# Nano_RC_Receiver.net
KiCad netlist of a schematic drawn in EAGLE
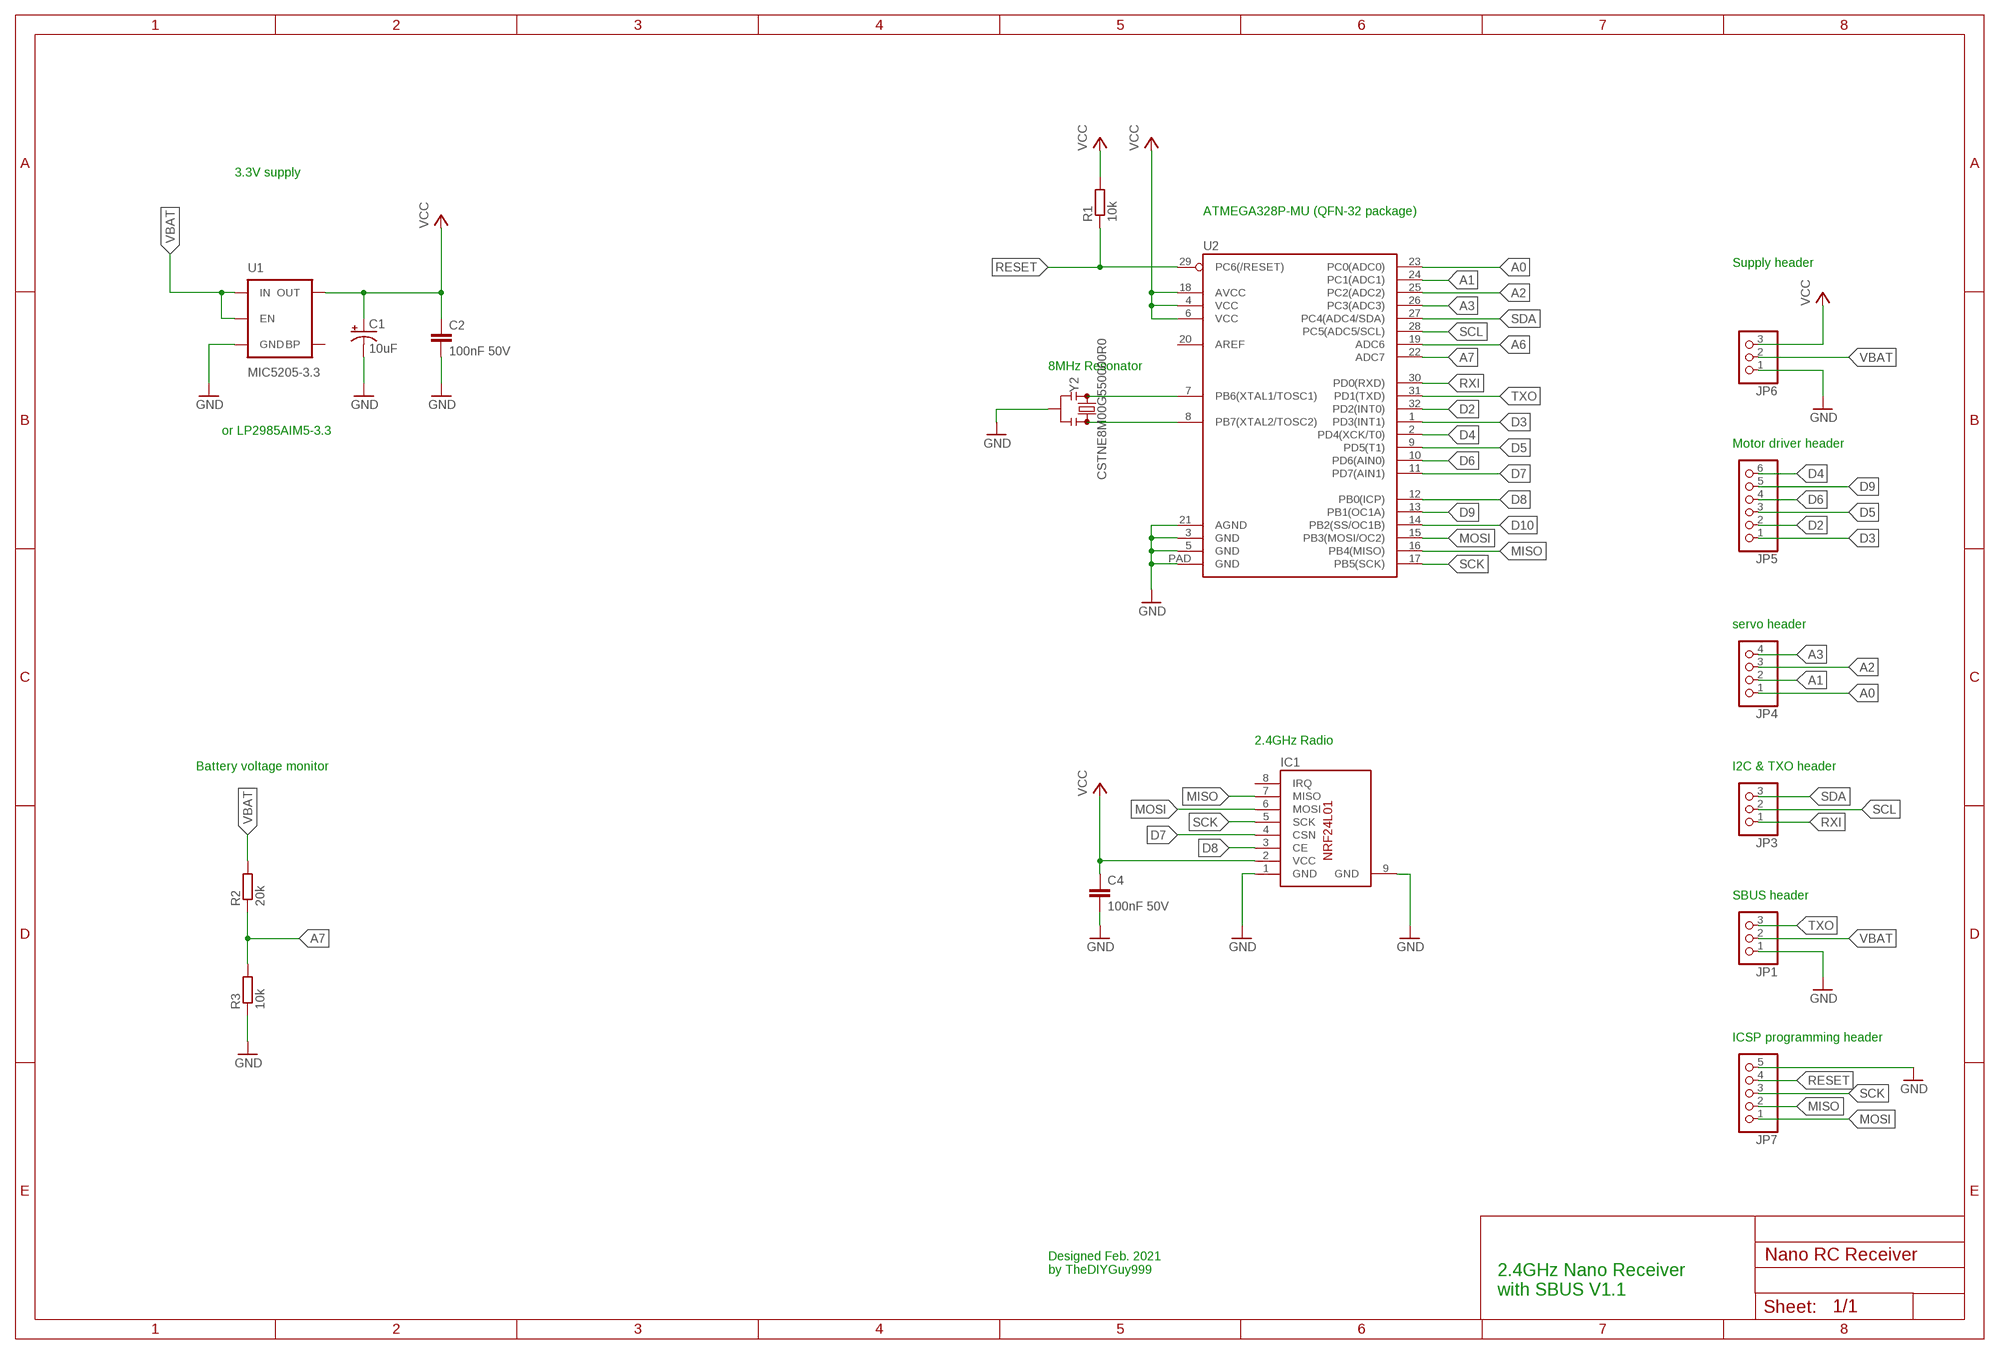
[diagram p0: schematic, sheet 1]

(export (version "E")
  (design (tool "Eeschema 10.0.6"))
  (components
    (comp (ref "C1")
      (value "10uF")
      (footprint "eagle-import:EIA3216")
      (libsource (lib "eagle-import") (part "10UF-16V-10%(TANT)"))
    )
    (comp (ref "C2")
      (value "100nF 50V")
      (footprint "eagle-import:C0603")
      (libsource (lib "eagle-import") (part "C-EUC0603"))
    )
    (comp (ref "C4")
      (value "100nF 50V")
      (footprint "eagle-import:C0603")
      (libsource (lib "eagle-import") (part "C-EUC0603"))
    )
    (comp (ref "IC1")
      (value "NRF24L01SMD_PAD")
      (footprint "eagle-import:NRF24L01_SMD_PAD")
      (libsource (lib "eagle-import") (part "NRF24L01SMD_PAD"))
    )
    (comp (ref "JP1")
      (value "PINHD-1X3SMT")
      (footprint "eagle-import:1X03_SMT")
      (libsource (lib "eagle-import") (part "PINHD-1X3SMT"))
    )
    (comp (ref "JP3")
      (value "PINHD-1X31.27")
      (footprint "eagle-import:1X03_1.27")
      (libsource (lib "eagle-import") (part "PINHD-1X31.27"))
    )
    (comp (ref "JP4")
      (value "PINHD-1X41.27")
      (footprint "eagle-import:1X04_1.27")
      (libsource (lib "eagle-import") (part "PINHD-1X41.27"))
    )
    (comp (ref "JP5")
      (value "PINHD-1X61.27")
      (footprint "eagle-import:1X06_1.27")
      (libsource (lib "eagle-import") (part "PINHD-1X61.27"))
    )
    (comp (ref "JP6")
      (value "PINHD-1X31.27")
      (footprint "eagle-import:1X03_1.27")
      (libsource (lib "eagle-import") (part "PINHD-1X31.27"))
    )
    (comp (ref "JP7")
      (value "PINHD-1X51.27")
      (footprint "eagle-import:1X05_1.27")
      (libsource (lib "eagle-import") (part "PINHD-1X51.27"))
    )
    (comp (ref "R1")
      (value "10k")
      (footprint "eagle-import:R0603")
      (libsource (lib "eagle-import") (part "R-EU_R0603"))
    )
    (comp (ref "R2")
      (value "20k")
      (footprint "eagle-import:R0603")
      (libsource (lib "eagle-import") (part "R-EU_R0603"))
    )
    (comp (ref "R3")
      (value "10k")
      (footprint "eagle-import:R0603")
      (libsource (lib "eagle-import") (part "R-EU_R0603"))
    )
    (comp (ref "U1")
      (value "MIC5205-3.3")
      (footprint "eagle-import:SOT23-5")
      (libsource (lib "eagle-import") (part "MIC52053.3V"))
    )
    (comp (ref "U2")
      (value "ATMEGA328P_MLFMLF32")
      (footprint "eagle-import:MLF32-PAD")
      (libsource (lib "eagle-import") (part "ATMEGA328P_MLFMLF32"))
    )
    (comp (ref "Y2")
      (value "CSTNE8M00G550000R0")
      (footprint "eagle-import:RESONATOR-SMD-3.2X1.3")
      (libsource (lib "eagle-import") (part "RESONATORSMD-3.2X1.3"))
    )
  )
  (nets
    (net (code "1") (name "A0") (class "Default")
      (node (ref "JP4") (pin "1") (pinfunction "1_1") (pintype "passive"))
      (node (ref "U2") (pin "23") (pinfunction "PC0(ADC0)_23") (pintype "bidirectional"))
    )
    (net (code "2") (name "A1") (class "Default")
      (node (ref "JP4") (pin "2") (pinfunction "2_2") (pintype "passive"))
      (node (ref "U2") (pin "24") (pinfunction "PC1(ADC1)_24") (pintype "bidirectional"))
    )
    (net (code "3") (name "A2") (class "Default")
      (node (ref "JP4") (pin "3") (pinfunction "3_3") (pintype "passive"))
      (node (ref "U2") (pin "25") (pinfunction "PC2(ADC2)_25") (pintype "bidirectional"))
    )
    (net (code "4") (name "A3") (class "Default")
      (node (ref "JP4") (pin "4") (pinfunction "4_4") (pintype "passive"))
      (node (ref "U2") (pin "26") (pinfunction "PC3(ADC3)_26") (pintype "bidirectional"))
    )
    (net (code "5") (name "A6") (class "Default")
      (node (ref "U2") (pin "19") (pinfunction "ADC6_19") (pintype "bidirectional"))
    )
    (net (code "6") (name "A7") (class "Default")
      (node (ref "R2") (pin "1") (pinfunction "1_1") (pintype "passive"))
      (node (ref "R3") (pin "2") (pinfunction "2_2") (pintype "passive"))
      (node (ref "U2") (pin "22") (pinfunction "ADC7_22") (pintype "bidirectional"))
    )
    (net (code "7") (name "D2") (class "Default")
      (node (ref "JP5") (pin "2") (pinfunction "2_2") (pintype "passive"))
      (node (ref "U2") (pin "32") (pinfunction "PD2(INT0)_32") (pintype "bidirectional"))
    )
    (net (code "8") (name "D3") (class "Default")
      (node (ref "JP5") (pin "1") (pinfunction "1_1") (pintype "passive"))
      (node (ref "U2") (pin "1") (pinfunction "PD3(INT1)_1") (pintype "bidirectional"))
    )
    (net (code "9") (name "D4") (class "Default")
      (node (ref "JP5") (pin "6") (pinfunction "6_6") (pintype "passive"))
      (node (ref "U2") (pin "2") (pinfunction "PD4(XCK/T0)_2") (pintype "bidirectional"))
    )
    (net (code "10") (name "D5") (class "Default")
      (node (ref "JP5") (pin "3") (pinfunction "3_3") (pintype "passive"))
      (node (ref "U2") (pin "9") (pinfunction "PD5(T1)_9") (pintype "bidirectional"))
    )
    (net (code "11") (name "D6") (class "Default")
      (node (ref "JP5") (pin "4") (pinfunction "4_4") (pintype "passive"))
      (node (ref "U2") (pin "10") (pinfunction "PD6(AIN0)_10") (pintype "bidirectional"))
    )
    (net (code "12") (name "D7") (class "Default")
      (node (ref "IC1") (pin "4") (pinfunction "CSN_4") (pintype "bidirectional"))
      (node (ref "U2") (pin "11") (pinfunction "PD7(AIN1)_11") (pintype "bidirectional"))
    )
    (net (code "13") (name "D8") (class "Default")
      (node (ref "IC1") (pin "3") (pinfunction "CE_3") (pintype "bidirectional"))
      (node (ref "U2") (pin "12") (pinfunction "PB0(ICP)_12") (pintype "bidirectional"))
    )
    (net (code "14") (name "D9") (class "Default")
      (node (ref "JP5") (pin "5") (pinfunction "5_5") (pintype "passive"))
      (node (ref "U2") (pin "13") (pinfunction "PB1(OC1A)_13") (pintype "bidirectional"))
    )
    (net (code "15") (name "D10") (class "Default")
      (node (ref "U2") (pin "14") (pinfunction "PB2(SS/OC1B)_14") (pintype "bidirectional"))
    )
    (net (code "16") (name "GND") (class "Default")
      (node (ref "C1") (pin "C") (pinfunction "-_C") (pintype "passive"))
      (node (ref "C2") (pin "2") (pinfunction "2_2") (pintype "passive"))
      (node (ref "C4") (pin "2") (pinfunction "2_2") (pintype "passive"))
      (node (ref "IC1") (pin "1") (pinfunction "GND_1") (pintype "bidirectional"))
      (node (ref "IC1") (pin "9") (pinfunction "GND_9") (pintype "bidirectional"))
      (node (ref "JP1") (pin "1") (pinfunction "1_1") (pintype "passive"))
      (node (ref "JP6") (pin "1") (pinfunction "1_1") (pintype "passive"))
      (node (ref "JP7") (pin "5") (pinfunction "5_5") (pintype "passive"))
      (node (ref "R3") (pin "1") (pinfunction "1_1") (pintype "passive"))
      (node (ref "U1") (pin "2") (pinfunction "GND_2") (pintype "input"))
      (node (ref "U2") (pin "21") (pinfunction "AGND_21") (pintype "bidirectional"))
      (node (ref "U2") (pin "3") (pinfunction "GND_3") (pintype "bidirectional"))
      (node (ref "U2") (pin "5") (pinfunction "GND_5") (pintype "bidirectional"))
      (node (ref "U2") (pin "PAD") (pinfunction "GND_PAD") (pintype "bidirectional"))
      (node (ref "Y2") (pin "2") (pinfunction "2_2") (pintype "passive"))
    )
    (net (code "17") (name "MISO") (class "Default")
      (node (ref "IC1") (pin "7") (pinfunction "MISO_7") (pintype "bidirectional"))
      (node (ref "JP7") (pin "2") (pinfunction "2_2") (pintype "passive"))
      (node (ref "U2") (pin "16") (pinfunction "PB4(MISO)_16") (pintype "bidirectional"))
    )
    (net (code "18") (name "MOSI") (class "Default")
      (node (ref "IC1") (pin "6") (pinfunction "MOSI_6") (pintype "bidirectional"))
      (node (ref "JP7") (pin "1") (pinfunction "1_1") (pintype "passive"))
      (node (ref "U2") (pin "15") (pinfunction "PB3(MOSI/OC2)_15") (pintype "bidirectional"))
    )
    (net (code "19") (name "Net-(U2-PB6(XTAL1{slash}TOSC1))") (class "Default")
      (node (ref "U2") (pin "7") (pinfunction "PB6(XTAL1/TOSC1)_7") (pintype "bidirectional"))
      (node (ref "Y2") (pin "1") (pinfunction "1_1") (pintype "passive"))
    )
    (net (code "20") (name "Net-(U2-PB7(XTAL2{slash}TOSC2))") (class "Default")
      (node (ref "U2") (pin "8") (pinfunction "PB7(XTAL2/TOSC2)_8") (pintype "bidirectional"))
      (node (ref "Y2") (pin "3") (pinfunction "3_3") (pintype "passive"))
    )
    (net (code "21") (name "RESET") (class "Default")
      (node (ref "JP7") (pin "4") (pinfunction "4_4") (pintype "passive"))
      (node (ref "R1") (pin "1") (pinfunction "1_1") (pintype "passive"))
      (node (ref "U2") (pin "29") (pinfunction "PC6(/RESET)_29") (pintype "bidirectional"))
    )
    (net (code "22") (name "RXI") (class "Default")
      (node (ref "JP3") (pin "1") (pinfunction "1_1") (pintype "passive"))
      (node (ref "U2") (pin "30") (pinfunction "PD0(RXD)_30") (pintype "bidirectional"))
    )
    (net (code "23") (name "SCK") (class "Default")
      (node (ref "IC1") (pin "5") (pinfunction "SCK_5") (pintype "bidirectional"))
      (node (ref "JP7") (pin "3") (pinfunction "3_3") (pintype "passive"))
      (node (ref "U2") (pin "17") (pinfunction "PB5(SCK)_17") (pintype "bidirectional"))
    )
    (net (code "24") (name "SCL") (class "Default")
      (node (ref "JP3") (pin "2") (pinfunction "2_2") (pintype "passive"))
      (node (ref "U2") (pin "28") (pinfunction "PC5(ADC5/SCL)_28") (pintype "bidirectional"))
    )
    (net (code "25") (name "SDA") (class "Default")
      (node (ref "JP3") (pin "3") (pinfunction "3_3") (pintype "passive"))
      (node (ref "U2") (pin "27") (pinfunction "PC4(ADC4/SDA)_27") (pintype "bidirectional"))
    )
    (net (code "26") (name "TXO") (class "Default")
      (node (ref "JP1") (pin "3") (pinfunction "3_3") (pintype "passive"))
      (node (ref "U2") (pin "31") (pinfunction "PD1(TXD)_31") (pintype "bidirectional"))
    )
    (net (code "27") (name "VBAT") (class "Default")
      (node (ref "JP1") (pin "2") (pinfunction "2_2") (pintype "passive"))
      (node (ref "JP6") (pin "2") (pinfunction "2_2") (pintype "passive"))
      (node (ref "R2") (pin "2") (pinfunction "2_2") (pintype "passive"))
      (node (ref "U1") (pin "1") (pinfunction "IN_1") (pintype "input"))
      (node (ref "U1") (pin "3") (pinfunction "EN_3") (pintype "input"))
    )
    (net (code "28") (name "VCC") (class "Default")
      (node (ref "C1") (pin "A") (pinfunction "+_A") (pintype "passive"))
      (node (ref "C2") (pin "1") (pinfunction "1_1") (pintype "passive"))
      (node (ref "C4") (pin "1") (pinfunction "1_1") (pintype "passive"))
      (node (ref "IC1") (pin "2") (pinfunction "VCC_2") (pintype "bidirectional"))
      (node (ref "JP6") (pin "3") (pinfunction "3_3") (pintype "passive"))
      (node (ref "R1") (pin "2") (pinfunction "2_2") (pintype "passive"))
      (node (ref "U1") (pin "5") (pinfunction "OUT_5") (pintype "passive"))
      (node (ref "U2") (pin "18") (pinfunction "AVCC_18") (pintype "bidirectional"))
      (node (ref "U2") (pin "4") (pinfunction "VCC_4") (pintype "bidirectional"))
      (node (ref "U2") (pin "6") (pinfunction "VCC_6") (pintype "bidirectional"))
    )
    (net (code "29") (name "unconnected-(IC1-IRQ-Pad8)") (class "Default")
      (node (ref "IC1") (pin "8") (pinfunction "IRQ_8") (pintype "bidirectional"))
    )
    (net (code "30") (name "unconnected-(U1-BP-Pad4)") (class "Default")
      (node (ref "U1") (pin "4") (pinfunction "BP_4") (pintype "input"))
    )
    (net (code "31") (name "unconnected-(U2-AREF-Pad20)") (class "Default")
      (node (ref "U2") (pin "20") (pinfunction "AREF_20") (pintype "bidirectional"))
    )
  )
)
